# rgb_circuit_diagram_1R.net
KiCad netlist of a schematic drawn in EAGLE
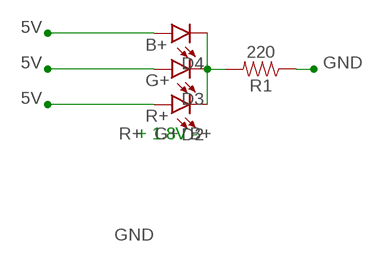
[diagram p0: schematic, sheet 1]

(export (version "E")
  (design (tool "Eeschema 10.0.6"))
  (components
    (comp (ref "D2")
      (value "LED-3MM-NO_SILK")
      (footprint "eagle-import:LED_3MM-NS")
      (libsource (lib "eagle-import") (part "LED-3MM-NO_SILK"))
    )
    (comp (ref "D3")
      (value "LED-3MM-NO_SILK")
      (footprint "eagle-import:LED_3MM-NS")
      (libsource (lib "eagle-import") (part "LED-3MM-NO_SILK"))
    )
    (comp (ref "D4")
      (value "LED-3MM-NO_SILK")
      (footprint "eagle-import:LED_3MM-NS")
      (libsource (lib "eagle-import") (part "LED-3MM-NO_SILK"))
    )
    (comp (ref "R1")
      (value "220")
      (footprint "eagle-import:0603")
      (libsource (lib "eagle-import") (part "220OHM-0603-1/10W-1%"))
    )
  )
  (nets
    (net (code "1") (name "/5V") (class "Default")
      (node (ref "D2") (pin "A") (pinfunction "A_A") (pintype "passive"))
    )
    (net (code "2") (name "/B+") (class "Default")
      (node (ref "D4") (pin "A") (pinfunction "A_A") (pintype "passive"))
    )
    (net (code "3") (name "/G+") (class "Default")
      (node (ref "D3") (pin "A") (pinfunction "A_A") (pintype "passive"))
    )
    (net (code "4") (name "/GND") (class "Default")
      (node (ref "D2") (pin "K") (pinfunction "C_K") (pintype "passive"))
      (node (ref "D3") (pin "K") (pinfunction "C_K") (pintype "passive"))
      (node (ref "D4") (pin "K") (pinfunction "C_K") (pintype "passive"))
      (node (ref "R1") (pin "2") (pinfunction "2_2") (pintype "passive"))
    )
    (net (code "5") (name "unconnected-(R1-Pad1)") (class "Default")
      (node (ref "R1") (pin "1") (pinfunction "1_1") (pintype "passive"))
    )
  )
)
